# RPi_Power_Injector.net
KiCad netlist of a schematic drawn in EAGLE
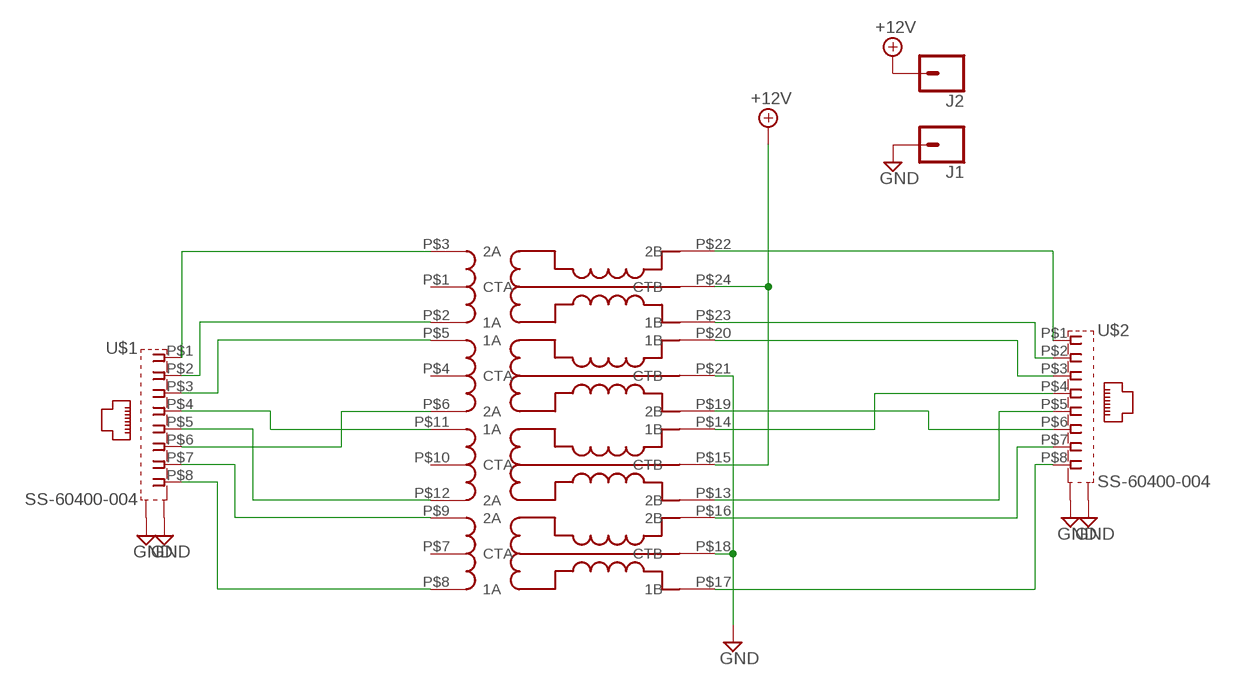
[diagram p0: schematic, sheet 1]

(export (version "E")
  (design (tool "Eeschema 10.0.6"))
  (components
    (comp (ref "J1")
      (value "CONN_01")
      (footprint "eagle-import:1X01")
      (libsource (lib "eagle-import") (part "CONN_01"))
    )
    (comp (ref "J2")
      (value "CONN_01")
      (footprint "eagle-import:1X01")
      (libsource (lib "eagle-import") (part "CONN_01"))
    )
    (comp (ref "U$1")
      (value "SS-60400-004")
      (footprint "eagle-import:SS-60400-004")
      (libsource (lib "eagle-import") (part "SS-60400-004"))
    )
    (comp (ref "U$2")
      (value "SS-60400-004")
      (footprint "eagle-import:SS-60400-004")
      (libsource (lib "eagle-import") (part "SS-60400-004"))
    )
    (comp (ref "U$3")
      (value "SM51589PEL")
      (footprint "eagle-import:SOIC-24-EW")
      (libsource (lib "eagle-import") (part "SM51589PEL"))
    )
  )
  (nets
    (net (code "1") (name "+12V") (class "Default")
      (node (ref "J2") (pin "1") (pinfunction "1_1") (pintype "passive"))
      (node (ref "U$3") (pin "P$15") (pinfunction "CTB_P$15") (pintype "bidirectional"))
      (node (ref "U$3") (pin "P$24") (pinfunction "CTB_P$24") (pintype "bidirectional"))
    )
    (net (code "2") (name "GND") (class "Default")
      (node (ref "J1") (pin "1") (pinfunction "1_1") (pintype "passive"))
      (node (ref "U$1") (pin "GND@1") (pinfunction "S1_GND@1") (pintype "passive"))
      (node (ref "U$1") (pin "GND@2") (pinfunction "S2_GND@2") (pintype "passive"))
      (node (ref "U$2") (pin "GND@1") (pinfunction "S1_GND@1") (pintype "passive"))
      (node (ref "U$2") (pin "GND@2") (pinfunction "S2_GND@2") (pintype "passive"))
      (node (ref "U$3") (pin "P$18") (pinfunction "CTB_P$18") (pintype "bidirectional"))
      (node (ref "U$3") (pin "P$21") (pinfunction "CTB_P$21") (pintype "bidirectional"))
    )
    (net (code "3") (name "Net-(U$1-1)") (class "Default")
      (node (ref "U$1") (pin "P$1") (pinfunction "1_P$1") (pintype "passive"))
      (node (ref "U$3") (pin "P$3") (pinfunction "2A_P$3") (pintype "bidirectional"))
    )
    (net (code "4") (name "Net-(U$1-2)") (class "Default")
      (node (ref "U$1") (pin "P$2") (pinfunction "2_P$2") (pintype "passive"))
      (node (ref "U$3") (pin "P$2") (pinfunction "1A_P$2") (pintype "bidirectional"))
    )
    (net (code "5") (name "Net-(U$1-3)") (class "Default")
      (node (ref "U$1") (pin "P$3") (pinfunction "3_P$3") (pintype "passive"))
      (node (ref "U$3") (pin "P$5") (pinfunction "1A_P$5") (pintype "bidirectional"))
    )
    (net (code "6") (name "Net-(U$1-4)") (class "Default")
      (node (ref "U$1") (pin "P$4") (pinfunction "4_P$4") (pintype "passive"))
      (node (ref "U$3") (pin "P$11") (pinfunction "1A_P$11") (pintype "bidirectional"))
    )
    (net (code "7") (name "Net-(U$1-5)") (class "Default")
      (node (ref "U$1") (pin "P$5") (pinfunction "5_P$5") (pintype "passive"))
      (node (ref "U$3") (pin "P$12") (pinfunction "2A_P$12") (pintype "bidirectional"))
    )
    (net (code "8") (name "Net-(U$1-6)") (class "Default")
      (node (ref "U$1") (pin "P$6") (pinfunction "6_P$6") (pintype "passive"))
      (node (ref "U$3") (pin "P$6") (pinfunction "2A_P$6") (pintype "bidirectional"))
    )
    (net (code "9") (name "Net-(U$1-7)") (class "Default")
      (node (ref "U$1") (pin "P$7") (pinfunction "7_P$7") (pintype "passive"))
      (node (ref "U$3") (pin "P$9") (pinfunction "2A_P$9") (pintype "bidirectional"))
    )
    (net (code "10") (name "Net-(U$1-8)") (class "Default")
      (node (ref "U$1") (pin "P$8") (pinfunction "8_P$8") (pintype "passive"))
      (node (ref "U$3") (pin "P$8") (pinfunction "1A_P$8") (pintype "bidirectional"))
    )
    (net (code "11") (name "Net-(U$2-1)") (class "Default")
      (node (ref "U$2") (pin "P$1") (pinfunction "1_P$1") (pintype "passive"))
      (node (ref "U$3") (pin "P$22") (pinfunction "2B_P$22") (pintype "bidirectional"))
    )
    (net (code "12") (name "Net-(U$2-2)") (class "Default")
      (node (ref "U$2") (pin "P$2") (pinfunction "2_P$2") (pintype "passive"))
      (node (ref "U$3") (pin "P$23") (pinfunction "1B_P$23") (pintype "bidirectional"))
    )
    (net (code "13") (name "Net-(U$2-3)") (class "Default")
      (node (ref "U$2") (pin "P$3") (pinfunction "3_P$3") (pintype "passive"))
      (node (ref "U$3") (pin "P$20") (pinfunction "1B_P$20") (pintype "bidirectional"))
    )
    (net (code "14") (name "Net-(U$2-4)") (class "Default")
      (node (ref "U$2") (pin "P$4") (pinfunction "4_P$4") (pintype "passive"))
      (node (ref "U$3") (pin "P$14") (pinfunction "1B_P$14") (pintype "bidirectional"))
    )
    (net (code "15") (name "Net-(U$2-5)") (class "Default")
      (node (ref "U$2") (pin "P$5") (pinfunction "5_P$5") (pintype "passive"))
      (node (ref "U$3") (pin "P$13") (pinfunction "2B_P$13") (pintype "bidirectional"))
    )
    (net (code "16") (name "Net-(U$2-6)") (class "Default")
      (node (ref "U$2") (pin "P$6") (pinfunction "6_P$6") (pintype "passive"))
      (node (ref "U$3") (pin "P$19") (pinfunction "2B_P$19") (pintype "bidirectional"))
    )
    (net (code "17") (name "Net-(U$2-7)") (class "Default")
      (node (ref "U$2") (pin "P$7") (pinfunction "7_P$7") (pintype "passive"))
      (node (ref "U$3") (pin "P$16") (pinfunction "2B_P$16") (pintype "bidirectional"))
    )
    (net (code "18") (name "Net-(U$2-8)") (class "Default")
      (node (ref "U$2") (pin "P$8") (pinfunction "8_P$8") (pintype "passive"))
      (node (ref "U$3") (pin "P$17") (pinfunction "1B_P$17") (pintype "bidirectional"))
    )
    (net (code "19") (name "unconnected-(U$3A-CTA-PadP$1)") (class "Default")
      (node (ref "U$3") (pin "P$1") (pinfunction "CTA_P$1") (pintype "bidirectional"))
    )
    (net (code "20") (name "unconnected-(U$3B-CTA-PadP$4)") (class "Default")
      (node (ref "U$3") (pin "P$4") (pinfunction "CTA_P$4") (pintype "bidirectional"))
    )
    (net (code "21") (name "unconnected-(U$3C-CTA-PadP$7)") (class "Default")
      (node (ref "U$3") (pin "P$7") (pinfunction "CTA_P$7") (pintype "bidirectional"))
    )
    (net (code "22") (name "unconnected-(U$3D-CTA-PadP$10)") (class "Default")
      (node (ref "U$3") (pin "P$10") (pinfunction "CTA_P$10") (pintype "bidirectional"))
    )
  )
)
